# Sheet1.net
KiCad netlist of a schematic drawn in Altium Designer
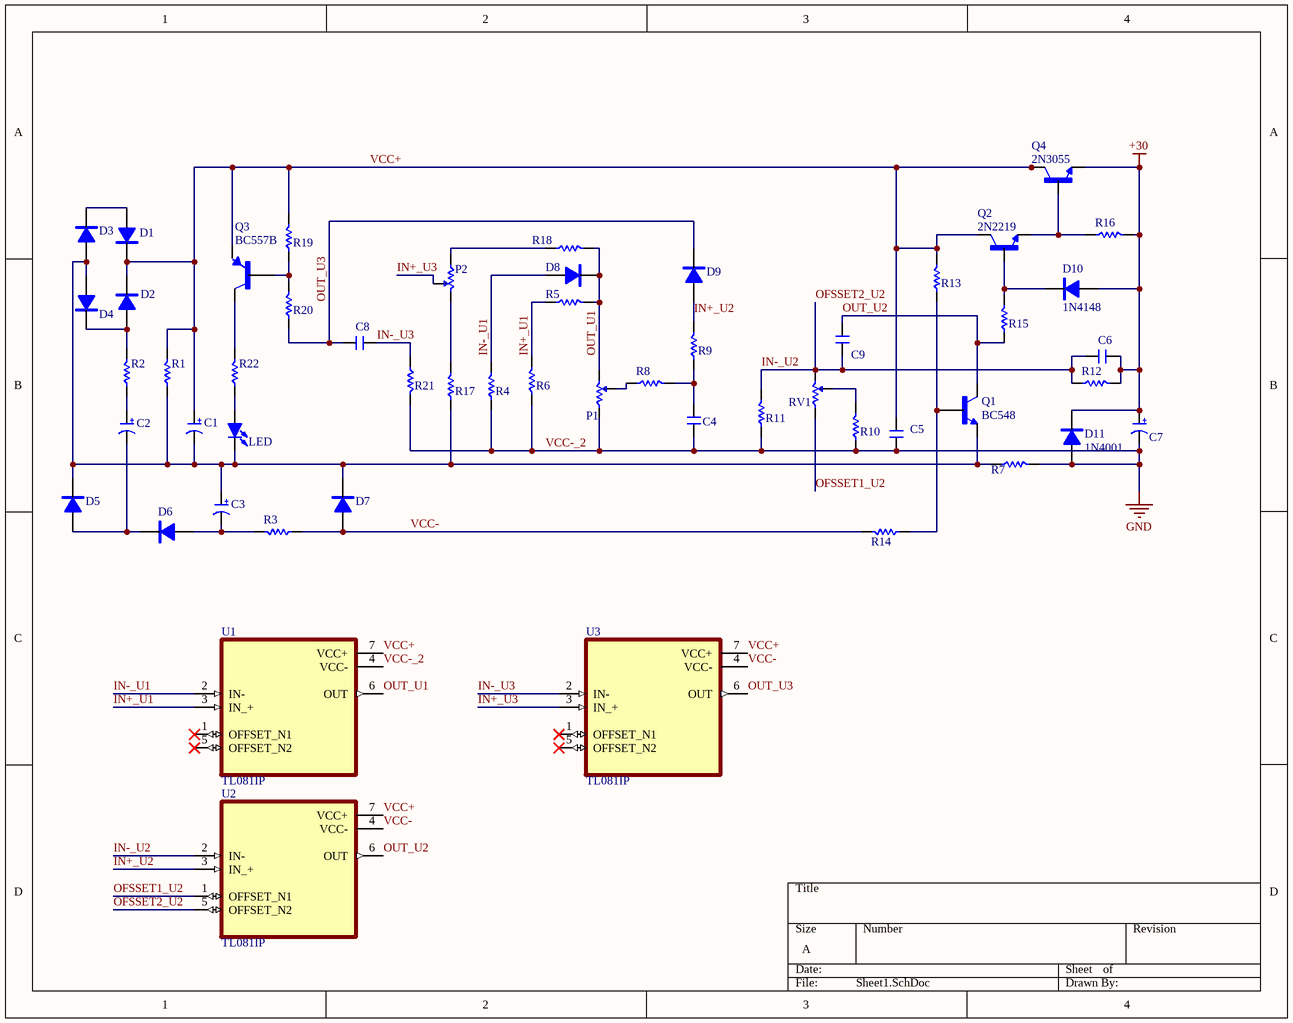
[diagram p0: Sheet1.SchDoc]

(export (version "E")
  (design (tool "Eeschema 10.0.6"))
  (components
    (comp (ref "C1")
      (value "3300uF/50V")
      (footprint "CAP 7.5*18*35.5-H - GD")
      (description "Inline electrolytic capacitor")
      (fields (field (name "版权归属") "源创客"))
      (libsource (lib "Passive (Resistor-Capacitor-Inductor-Veristor-Ferrite)") (part "C-CAP"))
    )
    (comp (ref "C2")
      (value "47uF/50V")
      (footprint "CAP 2.5*6.3*7")
      (description "Inline electrolytic capacitor")
      (fields (field (name "版权归属") "源创客"))
      (libsource (lib "Passive (Resistor-Capacitor-Inductor-Veristor-Ferrite)") (part "C-CAP"))
    )
    (comp (ref "C3")
      (value "47uF/50V")
      (footprint "CAP 2.5*6.3*7")
      (description "Inline electrolytic capacitor")
      (fields (field (name "版权归属") "源创客"))
      (libsource (lib "Passive (Resistor-Capacitor-Inductor-Veristor-Ferrite)") (part "C-CAP"))
    )
    (comp (ref "C4")
      (value "100nF///")
      (footprint "CBB 10*12*8")
      (description "CBB capacitor")
      (fields (field (name "版权归属") "源创客"))
      (libsource (lib "Passive (Resistor-Capacitor-Inductor-Veristor-Ferrite)") (part "C-CBB"))
    )
    (comp (ref "C5")
      (value "220nF")
      (footprint "CBB 10*12*8")
      (description "CBB capacitor")
      (fields (field (name "版权归属") "源创客"))
      (libsource (lib "Passive (Resistor-Capacitor-Inductor-Veristor-Ferrite)") (part "C-CBB"))
    )
    (comp (ref "C6")
      (value "100pF")
      (footprint "CC 2.2*5")
      (description "Straight insert ceramic capacitor")
      (fields (field (name "版权归属") "源创客"))
      (libsource (lib "Passive (Resistor-Capacitor-Inductor-Veristor-Ferrite)") (part "C-CC"))
    )
    (comp (ref "C7")
      (value "10uF/50V")
      (footprint "CAP 1.5*4*8")
      (description "Inline electrolytic capacitor")
      (fields (field (name "版权归属") "源创客"))
      (libsource (lib "Passive (Resistor-Capacitor-Inductor-Veristor-Ferrite)") (part "C-CAP"))
    )
    (comp (ref "C8")
      (value "330pF///")
      (footprint "CC 2.2*5")
      (description "Straight insert ceramic capacitor")
      (fields (field (name "版权归属") "源创客"))
      (libsource (lib "Passive (Resistor-Capacitor-Inductor-Veristor-Ferrite)") (part "C-CC"))
    )
    (comp (ref "C9")
      (value "100pF")
      (footprint "CC 2.2*5")
      (description "Straight insert ceramic capacitor")
      (fields (field (name "版权归属") "源创客"))
      (libsource (lib "Passive (Resistor-Capacitor-Inductor-Veristor-Ferrite)") (part "C-CC"))
    )
    (comp (ref "D1")
      (value "1N5402,3,4,5,6,7,8")
      (footprint "DO-41")
      (description "Rectifier diode")
      (fields (field (name "版权归属") "源创客"))
      (libsource (lib "Diode-Zener-Rectifier Bridge") (part "1N4007"))
    )
    (comp (ref "D2")
      (value "1N5402,3,4,5,6,7,8")
      (footprint "DO-41")
      (description "Rectifier diode")
      (fields (field (name "版权归属") "源创客"))
      (libsource (lib "Diode-Zener-Rectifier Bridge") (part "1N4007"))
    )
    (comp (ref "D3")
      (value "1N5402,3,4,5,6,7,8")
      (footprint "DO-41")
      (description "Rectifier diode")
      (fields (field (name "版权归属") "源创客"))
      (libsource (lib "Diode-Zener-Rectifier Bridge") (part "1N4007"))
    )
    (comp (ref "D4")
      (value "1N5402,3,4,5,6,7,8")
      (footprint "DO-41")
      (description "Rectifier diode")
      (fields (field (name "版权归属") "源创客"))
      (libsource (lib "Diode-Zener-Rectifier Bridge") (part "1N4007"))
    )
    (comp (ref "D5")
      (value "1N4148")
      (footprint "DO-35")
      (description "High speed switching diode")
      (fields (field (name "版权归属") "源创客"))
      (libsource (lib "Diode-Zener-Rectifier Bridge") (part "1N4148"))
    )
    (comp (ref "D6")
      (value "1N4148")
      (footprint "DO-35")
      (description "High speed switching diode")
      (fields (field (name "版权归属") "源创客"))
      (libsource (lib "Diode-Zener-Rectifier Bridge") (part "1N4148"))
    )
    (comp (ref "D7")
      (value "5,6V Zener")
      (footprint "DO-41")
      (description "Rectifier diode")
      (fields (field (name "版权归属") "源创客"))
      (libsource (lib "Diode-Zener-Rectifier Bridge") (part "1N4007"))
    )
    (comp (ref "D8")
      (value "5,6V Zener")
      (footprint "DO-41")
      (description "Rectifier diode")
      (fields (field (name "版权归属") "源创客"))
      (libsource (lib "Diode-Zener-Rectifier Bridge") (part "1N4007"))
    )
    (comp (ref "D9")
      (value "1N4148")
      (footprint "DO-35")
      (description "High speed switching diode")
      (fields (field (name "版权归属") "源创客"))
      (libsource (lib "Diode-Zener-Rectifier Bridge") (part "1N4148"))
    )
    (comp (ref "D10")
      (value "1N4148")
      (footprint "DO-35")
      (description "High speed switching diode")
      (fields (field (name "版权归属") "源创客"))
      (libsource (lib "Diode-Zener-Rectifier Bridge") (part "1N4148"))
    )
    (comp (ref "D11")
      (value "1N4001")
      (footprint "DO-41")
      (description "Rectifier diode")
      (fields (field (name "版权归属") "源创客"))
      (libsource (lib "Diode-Zener-Rectifier Bridge") (part "1N4007"))
    )
    (comp (ref "LED")
      (value "红色")
      (footprint "LED 5MM-R")
      (description "5mm plug-in LED")
      (fields (field (name "版权归属") "源创客"))
      (libsource (lib "LED") (part "LED-5MM"))
    )
    (comp (ref "P1")
      (value "~")
      (footprint "WH148")
      (description "Plug-in potentiometer")
      (fields (field (name "版权归属") "源创客"))
      (libsource (lib "Passive (Resistor-Capacitor-Inductor-Veristor-Ferrite)") (part "RP-THD"))
    )
    (comp (ref "P2")
      (value "~")
      (footprint "WH148")
      (description "Plug-in potentiometer")
      (fields (field (name "版权归属") "源创客"))
      (libsource (lib "Passive (Resistor-Capacitor-Inductor-Veristor-Ferrite)") (part "RP-THD"))
    )
    (comp (ref "Q1")
      (value "BC548")
      (footprint "TO92127P520H533-3")
      (description "Bipolar (BJT) Transistor NPN 30V 100mA 300MHz 500mW Through Hole TO-92-3")
      (fields (field (name "MF") "ON Semiconductor"))
      (libsource (lib "BC548") (part "BC548"))
    )
    (comp (ref "Q2")
      (value "2N2219")
      (footprint "TO5")
      (description "Bipolar _BJT_ Transistor NPN 30V 800mA 800mW Through Hole TO-39 _TO-205AD_")
      (fields (field (name "MF") "Microsemi"))
      (libsource (lib "2N2219") (part "2N2219"))
    )
    (comp (ref "Q3")
      (value "BC557B")
      (footprint "TO127P254X732-3")
      (description "Tranzistor bipolar _BJT_ PNP 45V 100mA 320MHz 625mW Gura de trecere TO-92-3")
      (fields (field (name "MF") "Diotec Semiconductor"))
      (libsource (lib "BC557B") (part "BC557B"))
    )
    (comp (ref "Q4")
      (value "2N3055")
      (footprint "TO3")
      (description "Bipolar _BJT_ Transistor NPN 60V 15A 2.5MHz 115W Through Hole TO-3")
      (fields (field (name "MF") "STMicroelectronics"))
      (libsource (lib "2N3055") (part "2N3055"))
    )
    (comp (ref "R1")
      (value "2.2K")
      (footprint "RS 1/4W")
      (description "Straight color ring resistor")
      (fields (field (name "版权归属") "源创客"))
      (libsource (lib "Passive (Resistor-Capacitor-Inductor-Veristor-Ferrite)") (part "R-CRR"))
    )
    (comp (ref "R2")
      (value "82")
      (footprint "RS 1/4W")
      (description "Straight color ring resistor")
      (fields (field (name "版权归属") "源创客"))
      (libsource (lib "Passive (Resistor-Capacitor-Inductor-Veristor-Ferrite)") (part "R-CRR"))
    )
    (comp (ref "R3")
      (value "220")
      (footprint "RS 1/4W")
      (description "Straight color ring resistor")
      (fields (field (name "版权归属") "源创客"))
      (libsource (lib "Passive (Resistor-Capacitor-Inductor-Veristor-Ferrite)") (part "R-CRR"))
    )
    (comp (ref "R4")
      (value "4.7K")
      (footprint "RS 1/4W")
      (description "Straight color ring resistor")
      (fields (field (name "版权归属") "源创客"))
      (libsource (lib "Passive (Resistor-Capacitor-Inductor-Veristor-Ferrite)") (part "R-CRR"))
    )
    (comp (ref "R5")
      (value "10K")
      (footprint "RS 1/4W")
      (description "Straight color ring resistor")
      (fields (field (name "版权归属") "源创客"))
      (libsource (lib "Passive (Resistor-Capacitor-Inductor-Veristor-Ferrite)") (part "R-CRR"))
    )
    (comp (ref "R6")
      (value "10K")
      (footprint "RS 1/4W")
      (description "Straight color ring resistor")
      (fields (field (name "版权归属") "源创客"))
      (libsource (lib "Passive (Resistor-Capacitor-Inductor-Veristor-Ferrite)") (part "R-CRR"))
    )
    (comp (ref "R7")
      (value "0.47")
      (footprint "RS 5W")
      (description "Straight color ring resistor")
      (fields (field (name "版权归属") "源创客"))
      (libsource (lib "Passive (Resistor-Capacitor-Inductor-Veristor-Ferrite)") (part "R-CRR"))
    )
    (comp (ref "R8")
      (value "27K")
      (footprint "RS 1/4W")
      (description "Straight color ring resistor")
      (fields (field (name "版权归属") "源创客"))
      (libsource (lib "Passive (Resistor-Capacitor-Inductor-Veristor-Ferrite)") (part "R-CRR"))
    )
    (comp (ref "R9")
      (value "2.2K")
      (footprint "RS 1/4W")
      (description "Straight color ring resistor")
      (fields (field (name "版权归属") "源创客"))
      (libsource (lib "Passive (Resistor-Capacitor-Inductor-Veristor-Ferrite)") (part "R-CRR"))
    )
    (comp (ref "R10")
      (value "270K")
      (footprint "RS 1/4W")
      (description "Straight color ring resistor")
      (fields (field (name "版权归属") "源创客"))
      (libsource (lib "Passive (Resistor-Capacitor-Inductor-Veristor-Ferrite)") (part "R-CRR"))
    )
    (comp (ref "R11")
      (value "27K")
      (footprint "RS 1/4W")
      (description "Straight color ring resistor")
      (fields (field (name "版权归属") "源创客"))
      (libsource (lib "Passive (Resistor-Capacitor-Inductor-Veristor-Ferrite)") (part "R-CRR"))
    )
    (comp (ref "R12")
      (value "56K")
      (footprint "RS 1/4W")
      (description "Straight color ring resistor")
      (fields (field (name "版权归属") "源创客"))
      (libsource (lib "Passive (Resistor-Capacitor-Inductor-Veristor-Ferrite)") (part "R-CRR"))
    )
    (comp (ref "R13")
      (value "10K")
      (footprint "RS 1/4W")
      (description "Straight color ring resistor")
      (fields (field (name "版权归属") "源创客"))
      (libsource (lib "Passive (Resistor-Capacitor-Inductor-Veristor-Ferrite)") (part "R-CRR"))
    )
    (comp (ref "R14")
      (value "1.5K")
      (footprint "RS 1/4W")
      (description "Straight color ring resistor")
      (fields (field (name "版权归属") "源创客"))
      (libsource (lib "Passive (Resistor-Capacitor-Inductor-Veristor-Ferrite)") (part "R-CRR"))
    )
    (comp (ref "R15")
      (value "1K")
      (footprint "RS 1/4W")
      (description "Straight color ring resistor")
      (fields (field (name "版权归属") "源创客"))
      (libsource (lib "Passive (Resistor-Capacitor-Inductor-Veristor-Ferrite)") (part "R-CRR"))
    )
    (comp (ref "R16")
      (value "1K")
      (footprint "RS 1/4W")
      (description "Straight color ring resistor")
      (fields (field (name "版权归属") "源创客"))
      (libsource (lib "Passive (Resistor-Capacitor-Inductor-Veristor-Ferrite)") (part "R-CRR"))
    )
    (comp (ref "R17")
      (value "33")
      (footprint "RS 1/4W")
      (description "Straight color ring resistor")
      (fields (field (name "版权归属") "源创客"))
      (libsource (lib "Passive (Resistor-Capacitor-Inductor-Veristor-Ferrite)") (part "R-CRR"))
    )
    (comp (ref "R18")
      (value "56K")
      (footprint "RS 1/4W")
      (description "Straight color ring resistor")
      (fields (field (name "版权归属") "源创客"))
      (libsource (lib "Passive (Resistor-Capacitor-Inductor-Veristor-Ferrite)") (part "R-CRR"))
    )
    (comp (ref "R19")
      (value "2.2K")
      (footprint "RS 1/4W")
      (description "Straight color ring resistor")
      (fields (field (name "版权归属") "源创客"))
      (libsource (lib "Passive (Resistor-Capacitor-Inductor-Veristor-Ferrite)") (part "R-CRR"))
    )
    (comp (ref "R20")
      (value "10K")
      (footprint "RS 1/4W")
      (description "Straight color ring resistor")
      (fields (field (name "版权归属") "源创客"))
      (libsource (lib "Passive (Resistor-Capacitor-Inductor-Veristor-Ferrite)") (part "R-CRR"))
    )
    (comp (ref "R21")
      (value "10K")
      (footprint "RS 1/4W")
      (description "Straight color ring resistor")
      (fields (field (name "版权归属") "源创客"))
      (libsource (lib "Passive (Resistor-Capacitor-Inductor-Veristor-Ferrite)") (part "R-CRR"))
    )
    (comp (ref "R22")
      (value "3.9K")
      (footprint "RS 1/4W")
      (description "Straight color ring resistor")
      (fields (field (name "版权归属") "源创客"))
      (libsource (lib "Passive (Resistor-Capacitor-Inductor-Veristor-Ferrite)") (part "R-CRR"))
    )
    (comp (ref "RV1")
      (value "100K")
      (footprint "3296W")
      (description "Plug-in potentiometer")
      (fields (field (name "版权归属") "源创客"))
      (libsource (lib "Passive (Resistor-Capacitor-Inductor-Veristor-Ferrite)") (part "RP-THD"))
    )
    (comp (ref "U1")
      (value "TL081IP")
      (footprint "DIP794W45P254L959H508Q8")
      (description "Amplificador operacional de entrada JFET de alta velocidad de respuesta 8-PDIP -40 a 85")
      (fields (field (name "MF") "Texas Instruments"))
      (libsource (lib "TL081IP") (part "TL081IP"))
    )
    (comp (ref "U2")
      (value "TL081IP")
      (footprint "DIP794W45P254L959H508Q8")
      (description "Amplificador operacional de entrada JFET de alta velocidad de respuesta 8-PDIP -40 a 85")
      (fields (field (name "MF") "Texas Instruments"))
      (libsource (lib "TL081IP") (part "TL081IP"))
    )
    (comp (ref "U3")
      (value "TL081IP")
      (footprint "DIP794W45P254L959H508Q8")
      (description "Amplificador operacional de entrada JFET de alta velocidad de respuesta 8-PDIP -40 a 85")
      (fields (field (name "MF") "Texas Instruments"))
      (libsource (lib "TL081IP") (part "TL081IP"))
    )
  )
  (nets
    (net (code "1") (name "+30") (class "Default")
      (node (ref "C6") (pin "2") (pinfunction "2_2") (pintype "passive"))
      (node (ref "C7") (pin "1") (pinfunction "A_1") (pintype "passive"))
      (node (ref "D10") (pin "1") (pinfunction "A_1") (pintype "passive"))
      (node (ref "D11") (pin "2") (pinfunction "K_2") (pintype "passive"))
      (node (ref "Q4") (pin "E") (pinfunction "E_E") (pintype "passive"))
      (node (ref "R12") (pin "2") (pinfunction "2_2") (pintype "passive"))
      (node (ref "R16") (pin "2") (pinfunction "2_2") (pintype "passive"))
    )
    (net (code "2") (name "/IN+_U1") (class "Default")
      (node (ref "R5") (pin "1") (pinfunction "1_1") (pintype "passive"))
      (node (ref "R6") (pin "2") (pinfunction "2_2") (pintype "passive"))
      (node (ref "U1") (pin "3") (pinfunction "IN_+_3") (pintype "input"))
    )
    (net (code "3") (name "/IN+_U2") (class "Default")
      (node (ref "D9") (pin "1") (pinfunction "A_1") (pintype "passive"))
      (node (ref "R9") (pin "2") (pinfunction "2_2") (pintype "passive"))
      (node (ref "U2") (pin "3") (pinfunction "IN_+_3") (pintype "input"))
    )
    (net (code "4") (name "/IN+_U3") (class "Default")
      (node (ref "P2") (pin "ADJ") (pinfunction "ADJ_ADJ") (pintype "passive"))
      (node (ref "U3") (pin "3") (pinfunction "IN_+_3") (pintype "input"))
    )
    (net (code "5") (name "/IN-_U1") (class "Default")
      (node (ref "D8") (pin "1") (pinfunction "A_1") (pintype "passive"))
      (node (ref "R4") (pin "2") (pinfunction "2_2") (pintype "passive"))
      (node (ref "U1") (pin "2") (pinfunction "IN-_2") (pintype "input"))
    )
    (net (code "6") (name "/IN-_U2") (class "Default")
      (node (ref "C6") (pin "1") (pinfunction "1_1") (pintype "passive"))
      (node (ref "C9") (pin "1") (pinfunction "1_1") (pintype "passive"))
      (node (ref "R11") (pin "2") (pinfunction "2_2") (pintype "passive"))
      (node (ref "R12") (pin "1") (pinfunction "1_1") (pintype "passive"))
      (node (ref "RV1") (pin "2") (pinfunction "2_2") (pintype "passive"))
      (node (ref "U2") (pin "2") (pinfunction "IN-_2") (pintype "input"))
      (node (ref "U2") (pin "5") (pinfunction "OFFSET_N2_5") (pintype "bidirectional"))
    )
    (net (code "7") (name "/IN-_U3") (class "Default")
      (node (ref "C8") (pin "1") (pinfunction "1_1") (pintype "passive"))
      (node (ref "R21") (pin "1") (pinfunction "1_1") (pintype "passive"))
      (node (ref "U3") (pin "2") (pinfunction "IN-_2") (pintype "input"))
    )
    (net (code "8") (name "/OFSSET1_U2") (class "Default")
      (node (ref "RV1") (pin "1") (pinfunction "1_1") (pintype "passive"))
      (node (ref "U2") (pin "1") (pinfunction "OFFSET_N1_1") (pintype "bidirectional"))
    )
    (net (code "9") (name "/OUT_U1") (class "Default")
      (node (ref "D8") (pin "2") (pinfunction "K_2") (pintype "passive"))
      (node (ref "P1") (pin "2") (pinfunction "2_2") (pintype "passive"))
      (node (ref "R18") (pin "2") (pinfunction "2_2") (pintype "passive"))
      (node (ref "R5") (pin "2") (pinfunction "2_2") (pintype "passive"))
      (node (ref "U1") (pin "6") (pinfunction "OUT_6") (pintype "output"))
    )
    (net (code "10") (name "/OUT_U2") (class "Default")
      (node (ref "C9") (pin "2") (pinfunction "2_2") (pintype "passive"))
      (node (ref "Q1") (pin "1") (pinfunction "C_1") (pintype "passive"))
      (node (ref "R15") (pin "1") (pinfunction "1_1") (pintype "passive"))
      (node (ref "U2") (pin "6") (pinfunction "OUT_6") (pintype "output"))
    )
    (net (code "11") (name "/OUT_U3") (class "Default")
      (node (ref "C8") (pin "2") (pinfunction "2_2") (pintype "passive"))
      (node (ref "D9") (pin "2") (pinfunction "K_2") (pintype "passive"))
      (node (ref "R20") (pin "1") (pinfunction "1_1") (pintype "passive"))
      (node (ref "U3") (pin "6") (pinfunction "OUT_6") (pintype "output"))
    )
    (net (code "12") (name "/VCC+") (class "Default")
      (node (ref "C1") (pin "1") (pinfunction "A_1") (pintype "passive"))
      (node (ref "C5") (pin "2") (pinfunction "2_2") (pintype "passive"))
      (node (ref "D1") (pin "2") (pinfunction "K_2") (pintype "passive"))
      (node (ref "D2") (pin "2") (pinfunction "K_2") (pintype "passive"))
      (node (ref "Q2") (pin "3") (pinfunction "C_3") (pintype "passive"))
      (node (ref "Q3") (pin "3") (pinfunction "E_3") (pintype "passive"))
      (node (ref "Q4") (pin "C") (pinfunction "C_C") (pintype "passive"))
      (node (ref "Q4") (pin "C/") (pinfunction "C_C/") (pintype "passive"))
      (node (ref "R1") (pin "2") (pinfunction "2_2") (pintype "passive"))
      (node (ref "R13") (pin "2") (pinfunction "2_2") (pintype "passive"))
      (node (ref "R19") (pin "2") (pinfunction "2_2") (pintype "passive"))
      (node (ref "U1") (pin "7") (pinfunction "VCC+_7") (pintype "power_in"))
      (node (ref "U2") (pin "7") (pinfunction "VCC+_7") (pintype "power_in"))
      (node (ref "U3") (pin "7") (pinfunction "VCC+_7") (pintype "power_in"))
    )
    (net (code "13") (name "/VCC-") (class "Default")
      (node (ref "D7") (pin "1") (pinfunction "A_1") (pintype "passive"))
      (node (ref "R14") (pin "2") (pinfunction "2_2") (pintype "passive"))
      (node (ref "R3") (pin "1") (pinfunction "1_1") (pintype "passive"))
      (node (ref "U2") (pin "4") (pinfunction "VCC-_4") (pintype "power_in"))
      (node (ref "U3") (pin "4") (pinfunction "VCC-_4") (pintype "power_in"))
    )
    (net (code "14") (name "GND") (class "Default")
      (node (ref "C4") (pin "1") (pinfunction "1_1") (pintype "passive"))
      (node (ref "C5") (pin "1") (pinfunction "1_1") (pintype "passive"))
      (node (ref "C7") (pin "2") (pinfunction "K_2") (pintype "passive"))
      (node (ref "D11") (pin "1") (pinfunction "A_1") (pintype "passive"))
      (node (ref "P1") (pin "1") (pinfunction "1_1") (pintype "passive"))
      (node (ref "R10") (pin "1") (pinfunction "1_1") (pintype "passive"))
      (node (ref "R11") (pin "1") (pinfunction "1_1") (pintype "passive"))
      (node (ref "R21") (pin "2") (pinfunction "2_2") (pintype "passive"))
      (node (ref "R4") (pin "1") (pinfunction "1_1") (pintype "passive"))
      (node (ref "R6") (pin "1") (pinfunction "1_1") (pintype "passive"))
      (node (ref "R7") (pin "2") (pinfunction "2_2") (pintype "passive"))
      (node (ref "U1") (pin "4") (pinfunction "VCC-_4") (pintype "power_in"))
    )
    (net (code "15") (name "Net-(C1-K)") (class "Default")
      (node (ref "C1") (pin "2") (pinfunction "K_2") (pintype "passive"))
      (node (ref "C3") (pin "1") (pinfunction "A_1") (pintype "passive"))
      (node (ref "D3") (pin "1") (pinfunction "A_1") (pintype "passive"))
      (node (ref "D4") (pin "1") (pinfunction "A_1") (pintype "passive"))
      (node (ref "D5") (pin "2") (pinfunction "K_2") (pintype "passive"))
      (node (ref "D7") (pin "2") (pinfunction "K_2") (pintype "passive"))
      (node (ref "LED") (pin "2") (pinfunction "K_2") (pintype "passive"))
      (node (ref "Q1") (pin "3") (pinfunction "E_3") (pintype "passive"))
      (node (ref "R1") (pin "1") (pinfunction "1_1") (pintype "passive"))
      (node (ref "R17") (pin "1") (pinfunction "1_1") (pintype "passive"))
      (node (ref "R7") (pin "1") (pinfunction "1_1") (pintype "passive"))
    )
    (net (code "16") (name "Net-(C2-A)") (class "Default")
      (node (ref "C2") (pin "1") (pinfunction "A_1") (pintype "passive"))
      (node (ref "R2") (pin "1") (pinfunction "1_1") (pintype "passive"))
    )
    (net (code "17") (name "Net-(C2-K)") (class "Default")
      (node (ref "C2") (pin "2") (pinfunction "K_2") (pintype "passive"))
      (node (ref "D5") (pin "1") (pinfunction "A_1") (pintype "passive"))
      (node (ref "D6") (pin "2") (pinfunction "K_2") (pintype "passive"))
    )
    (net (code "18") (name "Net-(C3-K)") (class "Default")
      (node (ref "C3") (pin "2") (pinfunction "K_2") (pintype "passive"))
      (node (ref "D6") (pin "1") (pinfunction "A_1") (pintype "passive"))
      (node (ref "R3") (pin "2") (pinfunction "2_2") (pintype "passive"))
    )
    (net (code "19") (name "Net-(C4-Pad2)") (class "Default")
      (node (ref "C4") (pin "2") (pinfunction "2_2") (pintype "passive"))
      (node (ref "R8") (pin "2") (pinfunction "2_2") (pintype "passive"))
      (node (ref "R9") (pin "1") (pinfunction "1_1") (pintype "passive"))
    )
    (net (code "20") (name "Net-(D1-A)") (class "Default")
      (node (ref "D1") (pin "1") (pinfunction "A_1") (pintype "passive"))
      (node (ref "D3") (pin "2") (pinfunction "K_2") (pintype "passive"))
    )
    (net (code "21") (name "Net-(D2-A)") (class "Default")
      (node (ref "D2") (pin "1") (pinfunction "A_1") (pintype "passive"))
      (node (ref "D4") (pin "2") (pinfunction "K_2") (pintype "passive"))
      (node (ref "R2") (pin "2") (pinfunction "2_2") (pintype "passive"))
    )
    (net (code "22") (name "Net-(D10-K)") (class "Default")
      (node (ref "D10") (pin "2") (pinfunction "K_2") (pintype "passive"))
      (node (ref "Q2") (pin "2") (pinfunction "B_2") (pintype "passive"))
      (node (ref "R15") (pin "2") (pinfunction "2_2") (pintype "passive"))
    )
    (net (code "23") (name "Net-(LED-A)") (class "Default")
      (node (ref "LED") (pin "1") (pinfunction "A_1") (pintype "passive"))
      (node (ref "R22") (pin "1") (pinfunction "1_1") (pintype "passive"))
    )
    (net (code "24") (name "Net-(P1-PadADJ)") (class "Default")
      (node (ref "P1") (pin "ADJ") (pinfunction "ADJ_ADJ") (pintype "passive"))
      (node (ref "R8") (pin "1") (pinfunction "1_1") (pintype "passive"))
    )
    (net (code "25") (name "Net-(P2-Pad1)") (class "Default")
      (node (ref "P2") (pin "1") (pinfunction "1_1") (pintype "passive"))
      (node (ref "R18") (pin "1") (pinfunction "1_1") (pintype "passive"))
    )
    (net (code "26") (name "Net-(P2-Pad2)") (class "Default")
      (node (ref "P2") (pin "2") (pinfunction "2_2") (pintype "passive"))
      (node (ref "R17") (pin "2") (pinfunction "2_2") (pintype "passive"))
    )
    (net (code "27") (name "Net-(Q1-B)") (class "Default")
      (node (ref "Q1") (pin "2") (pinfunction "B_2") (pintype "passive"))
      (node (ref "R13") (pin "1") (pinfunction "1_1") (pintype "passive"))
      (node (ref "R14") (pin "1") (pinfunction "1_1") (pintype "passive"))
    )
    (net (code "28") (name "Net-(Q2-E)") (class "Default")
      (node (ref "Q2") (pin "1") (pinfunction "E_1") (pintype "passive"))
      (node (ref "Q4") (pin "B") (pinfunction "B_B") (pintype "passive"))
      (node (ref "R16") (pin "1") (pinfunction "1_1") (pintype "passive"))
    )
    (net (code "29") (name "Net-(Q3-B)") (class "Default")
      (node (ref "Q3") (pin "2") (pinfunction "B_2") (pintype "passive"))
      (node (ref "R19") (pin "1") (pinfunction "1_1") (pintype "passive"))
      (node (ref "R20") (pin "2") (pinfunction "2_2") (pintype "passive"))
    )
    (net (code "30") (name "Net-(Q3-C)") (class "Default")
      (node (ref "Q3") (pin "1") (pinfunction "C_1") (pintype "passive"))
      (node (ref "R22") (pin "2") (pinfunction "2_2") (pintype "passive"))
    )
    (net (code "31") (name "Net-(R10-Pad2)") (class "Default")
      (node (ref "R10") (pin "2") (pinfunction "2_2") (pintype "passive"))
      (node (ref "RV1") (pin "ADJ") (pinfunction "ADJ_ADJ") (pintype "passive"))
    )
    (net (code "32") (name "unconnected-(U1-OFFSET_N1-Pad1)") (class "Default")
      (node (ref "U1") (pin "1") (pinfunction "OFFSET_N1_1") (pintype "bidirectional+no_connect"))
    )
    (net (code "33") (name "unconnected-(U1-OFFSET_N2-Pad5)") (class "Default")
      (node (ref "U1") (pin "5") (pinfunction "OFFSET_N2_5") (pintype "bidirectional+no_connect"))
    )
    (net (code "34") (name "unconnected-(U3-OFFSET_N1-Pad1)") (class "Default")
      (node (ref "U3") (pin "1") (pinfunction "OFFSET_N1_1") (pintype "bidirectional+no_connect"))
    )
    (net (code "35") (name "unconnected-(U3-OFFSET_N2-Pad5)") (class "Default")
      (node (ref "U3") (pin "5") (pinfunction "OFFSET_N2_5") (pintype "bidirectional+no_connect"))
    )
  )
)
